# ESP32.net
KiCad netlist of a schematic drawn in Altium Designer
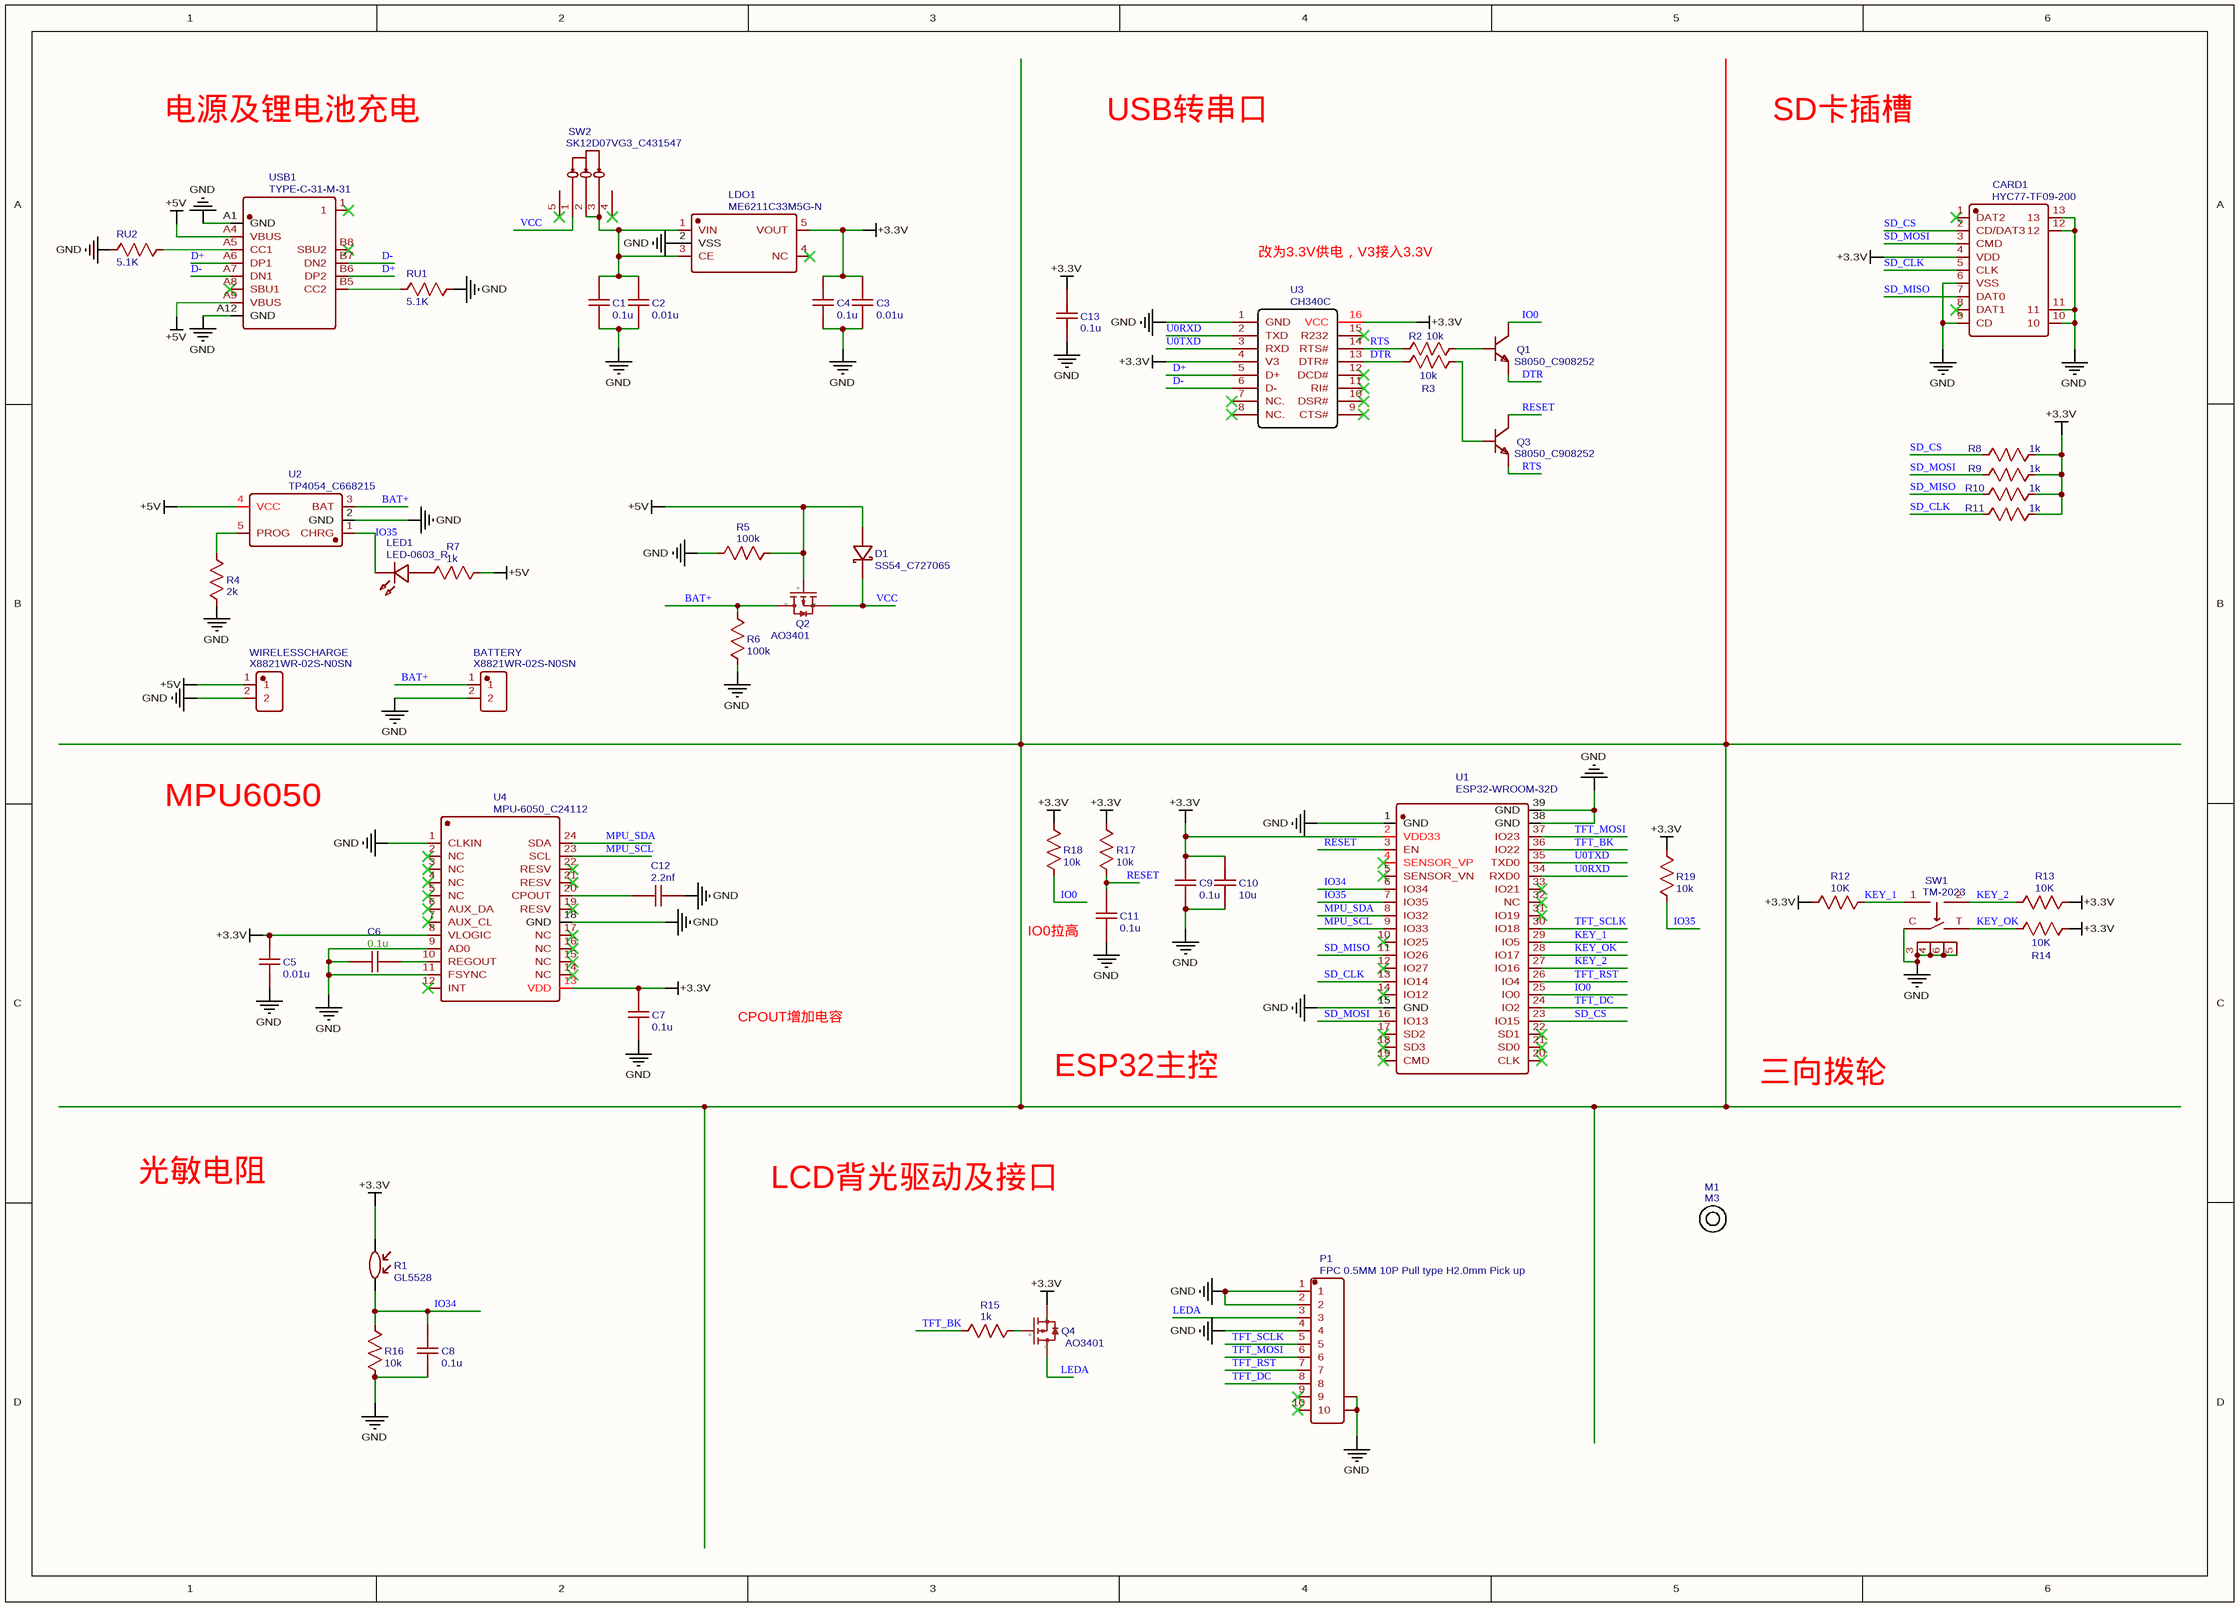
[diagram p0: ESP32花盆.schdoc]

(export (version "E")
  (design (tool "Eeschema 10.0.6"))
  (components
    (comp (ref "BATTERY")
      (value "X8821WR-02S-N0SN")
      (footprint "CONN-TH_X8821WR-02S-N0SN")
      (fields (field (name "BOM_SUPPLIER PART") "C388739") (field (name "CONTRIBUTOR") "LCSC"))
      (libsource (lib "altium-import") (part "root_0_X8821WR-02S-N0SN_"))
    )
    (comp (ref "C1")
      (value "0.1u")
      (footprint "C0603")
      (fields (field (name "CONTRIBUTOR") "LCEDA_Lib"))
      (libsource (lib "altium-import") (part "root_1_0.1u_"))
    )
    (comp (ref "C2")
      (value "0.01u")
      (footprint "C0603")
      (fields (field (name "CONTRIBUTOR") "LCEDA_Lib"))
      (libsource (lib "altium-import") (part "root_1_0.01u_"))
    )
    (comp (ref "C3")
      (value "0.01u")
      (footprint "C0603")
      (fields (field (name "CONTRIBUTOR") "LCEDA_Lib"))
      (libsource (lib "altium-import") (part "root_1_0.01u_"))
    )
    (comp (ref "C4")
      (value "0.1u")
      (footprint "C0603")
      (fields (field (name "CONTRIBUTOR") "LCEDA_Lib"))
      (libsource (lib "altium-import") (part "root_1_0.1u_"))
    )
    (comp (ref "C5")
      (value "0.01u")
      (footprint "C0603")
      (fields (field (name "CONTRIBUTOR") "LCEDA_Lib"))
      (libsource (lib "altium-import") (part "root_3_0.01u_"))
    )
    (comp (ref "C6")
      (value "0.1u")
      (footprint "C0603")
      (fields (field (name "CONTRIBUTOR") "LCEDA_Lib"))
      (libsource (lib "altium-import") (part "root_2_0.1u_"))
    )
    (comp (ref "C7")
      (value "0.1u")
      (footprint "C0603")
      (fields (field (name "CONTRIBUTOR") "LCEDA_Lib"))
      (libsource (lib "altium-import") (part "root_3_0.1u_"))
    )
    (comp (ref "C8")
      (value "0.1u")
      (footprint "C0603")
      (fields (field (name "CONTRIBUTOR") "LCEDA_Lib"))
      (libsource (lib "altium-import") (part "root_1_0.1u_"))
    )
    (comp (ref "C9")
      (value "0.1u")
      (footprint "C0603")
      (fields (field (name "CONTRIBUTOR") "LCEDA_Lib"))
      (libsource (lib "altium-import") (part "root_1_0.1u_"))
    )
    (comp (ref "C10")
      (value "10u")
      (footprint "C0603")
      (fields (field (name "CONTRIBUTOR") "LCEDA_Lib"))
      (libsource (lib "altium-import") (part "root_1_10u_"))
    )
    (comp (ref "C11")
      (value "0.1u")
      (footprint "C0603")
      (fields (field (name "CONTRIBUTOR") "LCEDA_Lib"))
      (libsource (lib "altium-import") (part "root_1_0.1u_"))
    )
    (comp (ref "C12")
      (value "2.2nf")
      (footprint "C0603")
      (fields (field (name "CONTRIBUTOR") "LCEDA_Lib"))
      (libsource (lib "altium-import") (part "root_0_2.2nf_"))
    )
    (comp (ref "C13")
      (value "0.1u")
      (footprint "C0603")
      (fields (field (name "CONTRIBUTOR") "LCEDA_Lib"))
      (libsource (lib "altium-import") (part "root_1_0.1u_"))
    )
    (comp (ref "CARD1")
      (value "HYC77-TF09-200")
      (footprint "TF-SMD_HYC77-TF09-200")
      (fields (field (name "BOM_SUPPLIER PART") "C341092") (field (name "CONTRIBUTOR") "LCSC"))
      (libsource (lib "altium-import") (part "root_0_HYC77-TF09-200_"))
    )
    (comp (ref "D1")
      (value "SS54_C727065")
      (footprint "SMA_L4.3-W2.6-LS5.0-RD")
      (fields
        (field (name "BOM_SUPPLIER PART") "C727065")
        (field (name "BOM_MANUFACTURER PART") "SS54")
        (field (name "CONTRIBUTOR") "LCSC")
      )
      (libsource (lib "altium-import") (part "root_1_SS54_C727065_"))
    )
    (comp (ref "LDO1")
      (value "ME6211C33M5G-N")
      (footprint "SOT-23-5_L3.0-W1.7-P0.95-LS2.8-BR")
      (fields (field (name "BOM_SUPPLIER PART") "C82942"))
      (libsource (lib "altium-import") (part "root_0_ME6211C33M5G-N_"))
    )
    (comp (ref "LED1")
      (value "LED-0603_R")
      (footprint "LED0603_RED")
      (fields
        (field (name "BOM_MANUFACTURER PART") "19-217/R6C-AL1M2VY/3T")
        (field (name "BOM_SUPPLIER PART") "C72044")
        (field (name "CONTRIBUTOR") "LCEDA_01")
      )
      (libsource (lib "altium-import") (part "root_2_LED-0603_R_"))
    )
    (comp (ref "M1")
      (value "M3")
      (footprint "M3")
      (fields (field (name "CONTRIBUTOR") "MengYang"))
      (libsource (lib "altium-import") (part "root_0_M3_"))
    )
    (comp (ref "P1")
      (value "FPC 0.5MM 10P Pull type H2.0mm Pick up")
      (footprint "FPC-SMD_FPC0.5MM10P")
      (fields (field (name "BOM_SUPPLIER PART") "C11085"))
      (libsource (lib "altium-import") (part "root_0_FPC 0.5MM 10P Pull type H2.0mm Pick up_"))
    )
    (comp (ref "Q1")
      (value "S8050_C908252")
      (footprint "SOT-23-3_L2.9-W1.3-P1.90-LS2.4-BR")
      (fields
        (field (name "BOM_SUPPLIER PART") "C908252")
        (field (name "BOM_MANUFACTURER PART") "S8050")
        (field (name "CONTRIBUTOR") "LCSC")
      )
      (libsource (lib "altium-import") (part "root_0_S8050_C908252_"))
    )
    (comp (ref "Q2")
      (value "AO3401")
      (footprint "SOT-23-3_L2.9-W1.3-P1.90-LS2.4-BR")
      (fields (field (name "BOM_SUPPLIER PART") "C181091") (field (name "CONTRIBUTOR") "LCSC"))
      (libsource (lib "altium-import") (part "root_3_AO3401_"))
    )
    (comp (ref "Q3")
      (value "S8050_C908252")
      (footprint "SOT-23-3_L2.9-W1.3-P1.90-LS2.4-BR")
      (fields
        (field (name "BOM_SUPPLIER PART") "C908252")
        (field (name "BOM_MANUFACTURER PART") "S8050")
        (field (name "CONTRIBUTOR") "LCSC")
      )
      (libsource (lib "altium-import") (part "root_0_S8050_C908252_"))
    )
    (comp (ref "Q4")
      (value "AO3401")
      (footprint "SOT-23-3_L2.9-W1.3-P1.90-LS2.4-BR")
      (fields (field (name "BOM_SUPPLIER PART") "C181091") (field (name "CONTRIBUTOR") "LCSC"))
      (libsource (lib "altium-import") (part "root_0_AO3401_"))
    )
    (comp (ref "R1")
      (value "GL5528")
      (footprint "RES-TH_L5.1-W4.3-P3.40-D0.5")
      (fields (field (name "BOM_SUPPLIER PART") "C125627"))
      (libsource (lib "altium-import") (part "root_3_GL5528_"))
    )
    (comp (ref "R2")
      (value "10k")
      (footprint "R0603")
      (fields (field (name "CONTRIBUTOR") "LCEDA_Lib"))
      (libsource (lib "altium-import") (part "root_0_10k_"))
    )
    (comp (ref "R3")
      (value "10k")
      (footprint "R0603")
      (fields (field (name "CONTRIBUTOR") "LCEDA_Lib"))
      (libsource (lib "altium-import") (part "root_0_10k_"))
    )
    (comp (ref "R4")
      (value "2k")
      (footprint "R0603")
      (fields (field (name "CONTRIBUTOR") "LCEDA_Lib"))
      (libsource (lib "altium-import") (part "root_1_2k_"))
    )
    (comp (ref "R5")
      (value "100k")
      (footprint "R0603")
      (fields (field (name "CONTRIBUTOR") "LCEDA_Lib"))
      (libsource (lib "altium-import") (part "root_0_100k_"))
    )
    (comp (ref "R6")
      (value "100k")
      (footprint "R0603")
      (fields (field (name "CONTRIBUTOR") "LCEDA_Lib"))
      (libsource (lib "altium-import") (part "root_1_100k_"))
    )
    (comp (ref "R7")
      (value "1k")
      (footprint "R0603")
      (fields (field (name "CONTRIBUTOR") "LCEDA_Lib"))
      (libsource (lib "altium-import") (part "root_0_1k_"))
    )
    (comp (ref "R8")
      (value "1k")
      (footprint "R0603")
      (fields (field (name "CONTRIBUTOR") "LCEDA_Lib"))
      (libsource (lib "altium-import") (part "root_0_1k_"))
    )
    (comp (ref "R9")
      (value "1k")
      (footprint "R0603")
      (fields (field (name "CONTRIBUTOR") "LCEDA_Lib"))
      (libsource (lib "altium-import") (part "root_0_1k_"))
    )
    (comp (ref "R10")
      (value "1k")
      (footprint "R0603")
      (fields (field (name "CONTRIBUTOR") "LCEDA_Lib"))
      (libsource (lib "altium-import") (part "root_0_1k_"))
    )
    (comp (ref "R11")
      (value "1k")
      (footprint "R0603")
      (fields (field (name "CONTRIBUTOR") "LCEDA_Lib"))
      (libsource (lib "altium-import") (part "root_0_1k_"))
    )
    (comp (ref "R12")
      (value "10K")
      (footprint "R0603")
      (fields (field (name "CONTRIBUTOR") "LCEDA_Lib"))
      (libsource (lib "altium-import") (part "root_2_10K_"))
    )
    (comp (ref "R13")
      (value "10K")
      (footprint "R0603")
      (fields (field (name "CONTRIBUTOR") "LCEDA_Lib"))
      (libsource (lib "altium-import") (part "root_2_10K_"))
    )
    (comp (ref "R14")
      (value "10K")
      (footprint "R0603")
      (fields (field (name "CONTRIBUTOR") "LCEDA_Lib"))
      (libsource (lib "altium-import") (part "root_2_10K_"))
    )
    (comp (ref "R15")
      (value "1k")
      (footprint "R0603")
      (fields (field (name "CONTRIBUTOR") "LCEDA_Lib"))
      (libsource (lib "altium-import") (part "root_0_1k_"))
    )
    (comp (ref "R16")
      (value "10k")
      (footprint "R0603")
      (fields (field (name "CONTRIBUTOR") "LCEDA_Lib"))
      (libsource (lib "altium-import") (part "root_1_10k_"))
    )
    (comp (ref "R17")
      (value "10k")
      (footprint "R0603")
      (fields (field (name "CONTRIBUTOR") "LCEDA_Lib"))
      (libsource (lib "altium-import") (part "root_1_10k_"))
    )
    (comp (ref "R18")
      (value "10k")
      (footprint "R0603")
      (fields (field (name "CONTRIBUTOR") "LCEDA_Lib"))
      (libsource (lib "altium-import") (part "root_1_10k_"))
    )
    (comp (ref "R19")
      (value "10k")
      (footprint "R0603")
      (fields (field (name "CONTRIBUTOR") "LCEDA_Lib"))
      (libsource (lib "altium-import") (part "root_1_10k_"))
    )
    (comp (ref "RU1")
      (value "5.1K")
      (footprint "R0603")
      (fields (field (name "CONTRIBUTOR") "LCEDA_Lib"))
      (libsource (lib "altium-import") (part "root_2_100k_"))
    )
    (comp (ref "RU2")
      (value "5.1K")
      (footprint "R0603")
      (fields (field (name "CONTRIBUTOR") "LCEDA_Lib"))
      (libsource (lib "altium-import") (part "root_2_100k_"))
    )
    (comp (ref "SW1")
      (value "TM-2023")
      (footprint "SW-SMD_TM-2023-1")
      (fields (field (name "BOM_SUPPLIER PART") "C318951") (field (name "CONTRIBUTOR") "LCSC"))
      (libsource (lib "altium-import") (part "root_0_TM-2023_"))
    )
    (comp (ref "SW2")
      (value "SK12D07VG3_C431547")
      (footprint "SW-TH_SK12D07VG3")
      (fields
        (field (name "BOM_SUPPLIER PART") "C431547")
        (field (name "BOM_MANUFACTURER PART") "SK12D07VG3")
        (field (name "CONTRIBUTOR") "LCSC")
      )
      (libsource (lib "altium-import") (part "root_0_SK12D07VG3_C431547_"))
    )
    (comp (ref "U1")
      (value "ESP32-WROOM-32D")
      (footprint "WIFIM-SMD_39P-L25.5-W18.0-P1.27-BL")
      (fields (field (name "BOM_SUPPLIER PART") "C473012") (field (name "CONTRIBUTOR") "LCSC"))
      (libsource (lib "altium-import") (part "root_0_ESP32-WROOM-32D_"))
    )
    (comp (ref "U2")
      (value "TP4054_C668215")
      (footprint "SOT-23-5_L3.0-W1.7-P0.95-LS2.8-BL")
      (fields
        (field (name "BOM_SUPPLIER PART") "C668215")
        (field (name "BOM_MANUFACTURER PART") "TP4054")
        (field (name "CONTRIBUTOR") "LCSC")
      )
      (libsource (lib "altium-import") (part "root_2_TP4054_C668215_"))
    )
    (comp (ref "U3")
      (value "CH340C")
      (footprint "SOP-16_L10.0-W3.9-P1.27-LS6.0-BL")
      (fields (field (name "BOM_SUPPLIER PART") "C84681"))
      (libsource (lib "altium-import") (part "root_0_CH340C_"))
    )
    (comp (ref "U4")
      (value "MPU-6050_C24112")
      (footprint "QFN-24_L4.0-W4.0-P0.50-BL-MPU-6050")
      (fields (field (name "BOM_MANUFACTURER PART") "MPU-6050") (field (name "BOM_SUPPLIER PART") "C24112"))
      (libsource (lib "altium-import") (part "root_0_MPU-6050_C24112_"))
    )
    (comp (ref "USB1")
      (value "TYPE-C-31-M-31")
      (footprint "USB-C-SMD_TYPE-C-31-M-31")
      (fields (field (name "BOM_SUPPLIER PART") "C2760486") (field (name "CONTRIBUTOR") "LCSC"))
      (libsource (lib "altium-import") (part "root_0_TYPE-C-31-M-31_"))
    )
    (comp (ref "WIRELESSCHARGE")
      (value "X8821WR-02S-N0SN")
      (footprint "CONN-TH_X8821WR-02S-N0SN")
      (fields (field (name "BOM_SUPPLIER PART") "C388739") (field (name "CONTRIBUTOR") "LCSC"))
      (libsource (lib "altium-import") (part "root_0_X8821WR-02S-N0SN_"))
    )
  )
  (nets
    (net (code "1") (name "+3.3V") (class "Default")
      (node (ref "C10") (pin "2") (pinfunction "2_2") (pintype "passive"))
      (node (ref "C13") (pin "2") (pinfunction "2_2") (pintype "passive"))
      (node (ref "C3") (pin "2") (pinfunction "2_2") (pintype "passive"))
      (node (ref "C4") (pin "2") (pinfunction "2_2") (pintype "passive"))
      (node (ref "C5") (pin "1") (pinfunction "1_1") (pintype "passive"))
      (node (ref "C7") (pin "1") (pinfunction "1_1") (pintype "passive"))
      (node (ref "C9") (pin "2") (pinfunction "2_2") (pintype "passive"))
      (node (ref "CARD1") (pin "4") (pinfunction "VDD_4") (pintype "passive"))
      (node (ref "LDO1") (pin "5") (pinfunction "VOUT_5") (pintype "passive"))
      (node (ref "Q4") (pin "2") (pinfunction "S_2") (pintype "passive"))
      (node (ref "R1") (pin "1") (pinfunction "1_1") (pintype "passive"))
      (node (ref "R10") (pin "2") (pinfunction "2_2") (pintype "passive"))
      (node (ref "R11") (pin "2") (pinfunction "2_2") (pintype "passive"))
      (node (ref "R12") (pin "2") (pinfunction "2_2") (pintype "passive"))
      (node (ref "R13") (pin "1") (pinfunction "1_1") (pintype "passive"))
      (node (ref "R14") (pin "1") (pinfunction "1_1") (pintype "passive"))
      (node (ref "R17") (pin "2") (pinfunction "2_2") (pintype "passive"))
      (node (ref "R18") (pin "2") (pinfunction "2_2") (pintype "passive"))
      (node (ref "R19") (pin "2") (pinfunction "2_2") (pintype "passive"))
      (node (ref "R8") (pin "2") (pinfunction "2_2") (pintype "passive"))
      (node (ref "R9") (pin "2") (pinfunction "2_2") (pintype "passive"))
      (node (ref "U1") (pin "2") (pinfunction "VDD33_2") (pintype "passive"))
      (node (ref "U3") (pin "16") (pinfunction "VCC_16") (pintype "passive"))
      (node (ref "U3") (pin "4") (pinfunction "V3_4") (pintype "passive"))
      (node (ref "U4") (pin "13") (pinfunction "VDD_13") (pintype "passive"))
      (node (ref "U4") (pin "8") (pinfunction "VLOGIC_8") (pintype "passive"))
    )
    (net (code "2") (name "+5V") (class "Default")
      (node (ref "D1") (pin "2") (pinfunction "2_2") (pintype "passive"))
      (node (ref "Q2") (pin "1") (pinfunction "G_1") (pintype "passive"))
      (node (ref "R5") (pin "2") (pinfunction "2_2") (pintype "passive"))
      (node (ref "R7") (pin "2") (pinfunction "2_2") (pintype "passive"))
      (node (ref "U2") (pin "4") (pinfunction "VCC_4") (pintype "passive"))
      (node (ref "USB1") (pin "A4") (pinfunction "VBUS_A4") (pintype "passive"))
      (node (ref "USB1") (pin "A9") (pinfunction "VBUS_A9") (pintype "passive"))
      (node (ref "WIRELESSCHARGE") (pin "1") (pinfunction "1_1") (pintype "passive"))
    )
    (net (code "3") (name "/BAT+") (class "Default")
      (node (ref "BATTERY") (pin "1") (pinfunction "1_1") (pintype "passive"))
      (node (ref "Q2") (pin "3") (pinfunction "D_3") (pintype "passive"))
      (node (ref "R6") (pin "2") (pinfunction "2_2") (pintype "passive"))
      (node (ref "U2") (pin "3") (pinfunction "BAT_3") (pintype "passive"))
    )
    (net (code "4") (name "/D+") (class "Default")
      (node (ref "U3") (pin "5") (pinfunction "D+_5") (pintype "passive"))
      (node (ref "USB1") (pin "A6") (pinfunction "DP1_A6") (pintype "passive"))
      (node (ref "USB1") (pin "B6") (pinfunction "DP2_B6") (pintype "passive"))
    )
    (net (code "5") (name "/D-") (class "Default")
      (node (ref "U3") (pin "6") (pinfunction "D-_6") (pintype "passive"))
      (node (ref "USB1") (pin "A7") (pinfunction "DN1_A7") (pintype "passive"))
      (node (ref "USB1") (pin "B7") (pinfunction "DN2_B7") (pintype "passive"))
    )
    (net (code "6") (name "/DTR") (class "Default")
      (node (ref "Q1") (pin "2") (pinfunction "E_2") (pintype "passive"))
      (node (ref "R3") (pin "1") (pinfunction "1_1") (pintype "passive"))
      (node (ref "U3") (pin "13") (pinfunction "DTR#_13") (pintype "passive"))
    )
    (net (code "7") (name "/IO0") (class "Default")
      (node (ref "Q1") (pin "3") (pinfunction "C_3") (pintype "passive"))
      (node (ref "R18") (pin "1") (pinfunction "1_1") (pintype "passive"))
      (node (ref "U1") (pin "25") (pinfunction "IO0_25") (pintype "passive"))
    )
    (net (code "8") (name "/IO34") (class "Default")
      (node (ref "C8") (pin "2") (pinfunction "2_2") (pintype "passive"))
      (node (ref "R1") (pin "2") (pinfunction "2_2") (pintype "passive"))
      (node (ref "R16") (pin "2") (pinfunction "2_2") (pintype "passive"))
      (node (ref "U1") (pin "6") (pinfunction "IO34_6") (pintype "passive"))
    )
    (net (code "9") (name "/IO35") (class "Default")
      (node (ref "LED1") (pin "2") (pinfunction "2_2") (pintype "passive"))
      (node (ref "R19") (pin "1") (pinfunction "1_1") (pintype "passive"))
      (node (ref "U1") (pin "7") (pinfunction "IO35_7") (pintype "passive"))
      (node (ref "U2") (pin "1") (pinfunction "CHRG_1") (pintype "passive"))
    )
    (net (code "10") (name "/KEY_1") (class "Default")
      (node (ref "R12") (pin "1") (pinfunction "1_1") (pintype "passive"))
      (node (ref "SW1") (pin "1") (pinfunction "1_1") (pintype "passive"))
      (node (ref "U1") (pin "29") (pinfunction "IO5_29") (pintype "passive"))
    )
    (net (code "11") (name "/KEY_2") (class "Default")
      (node (ref "R13") (pin "2") (pinfunction "2_2") (pintype "passive"))
      (node (ref "SW1") (pin "2") (pinfunction "2_2") (pintype "passive"))
      (node (ref "U1") (pin "27") (pinfunction "IO16_27") (pintype "passive"))
    )
    (net (code "12") (name "/KEY_OK") (class "Default")
      (node (ref "R14") (pin "2") (pinfunction "2_2") (pintype "passive"))
      (node (ref "SW1") (pin "T") (pinfunction "T_T") (pintype "passive"))
      (node (ref "U1") (pin "28") (pinfunction "IO17_28") (pintype "passive"))
    )
    (net (code "13") (name "/LEDA") (class "Default")
      (node (ref "P1") (pin "3") (pinfunction "3_3") (pintype "passive"))
      (node (ref "Q4") (pin "3") (pinfunction "D_3") (pintype "passive"))
    )
    (net (code "14") (name "/MPU_SCL") (class "Default")
      (node (ref "U1") (pin "9") (pinfunction "IO33_9") (pintype "passive"))
      (node (ref "U4") (pin "23") (pinfunction "SCL_23") (pintype "passive"))
    )
    (net (code "15") (name "/MPU_SDA") (class "Default")
      (node (ref "U1") (pin "8") (pinfunction "IO32_8") (pintype "passive"))
      (node (ref "U4") (pin "24") (pinfunction "SDA_24") (pintype "passive"))
    )
    (net (code "16") (name "/RESET") (class "Default")
      (node (ref "C11") (pin "2") (pinfunction "2_2") (pintype "passive"))
      (node (ref "Q3") (pin "3") (pinfunction "C_3") (pintype "passive"))
      (node (ref "R17") (pin "1") (pinfunction "1_1") (pintype "passive"))
      (node (ref "U1") (pin "3") (pinfunction "EN_3") (pintype "passive"))
    )
    (net (code "17") (name "/RTS") (class "Default")
      (node (ref "Q3") (pin "2") (pinfunction "E_2") (pintype "passive"))
      (node (ref "R2") (pin "1") (pinfunction "1_1") (pintype "passive"))
      (node (ref "U3") (pin "14") (pinfunction "RTS#_14") (pintype "passive"))
    )
    (net (code "18") (name "/SD_CLK") (class "Default")
      (node (ref "CARD1") (pin "5") (pinfunction "CLK_5") (pintype "passive"))
      (node (ref "R11") (pin "1") (pinfunction "1_1") (pintype "passive"))
      (node (ref "U1") (pin "13") (pinfunction "IO14_13") (pintype "passive"))
    )
    (net (code "19") (name "/SD_CS") (class "Default")
      (node (ref "CARD1") (pin "2") (pinfunction "CD/DAT3_2") (pintype "passive"))
      (node (ref "R8") (pin "1") (pinfunction "1_1") (pintype "passive"))
      (node (ref "U1") (pin "23") (pinfunction "IO15_23") (pintype "passive"))
    )
    (net (code "20") (name "/SD_MISO") (class "Default")
      (node (ref "CARD1") (pin "7") (pinfunction "DAT0_7") (pintype "passive"))
      (node (ref "R10") (pin "1") (pinfunction "1_1") (pintype "passive"))
      (node (ref "U1") (pin "11") (pinfunction "IO26_11") (pintype "passive"))
    )
    (net (code "21") (name "/SD_MOSI") (class "Default")
      (node (ref "CARD1") (pin "3") (pinfunction "CMD_3") (pintype "passive"))
      (node (ref "R9") (pin "1") (pinfunction "1_1") (pintype "passive"))
      (node (ref "U1") (pin "16") (pinfunction "IO13_16") (pintype "passive"))
    )
    (net (code "22") (name "/TFT_BK") (class "Default")
      (node (ref "R15") (pin "1") (pinfunction "1_1") (pintype "passive"))
      (node (ref "U1") (pin "36") (pinfunction "IO22_36") (pintype "passive"))
    )
    (net (code "23") (name "/TFT_DC") (class "Default")
      (node (ref "P1") (pin "8") (pinfunction "8_8") (pintype "passive"))
      (node (ref "U1") (pin "24") (pinfunction "IO2_24") (pintype "passive"))
    )
    (net (code "24") (name "/TFT_MOSI") (class "Default")
      (node (ref "P1") (pin "6") (pinfunction "6_6") (pintype "passive"))
      (node (ref "U1") (pin "37") (pinfunction "IO23_37") (pintype "passive"))
    )
    (net (code "25") (name "/TFT_RST") (class "Default")
      (node (ref "P1") (pin "7") (pinfunction "7_7") (pintype "passive"))
      (node (ref "U1") (pin "26") (pinfunction "IO4_26") (pintype "passive"))
    )
    (net (code "26") (name "/TFT_SCLK") (class "Default")
      (node (ref "P1") (pin "5") (pinfunction "5_5") (pintype "passive"))
      (node (ref "U1") (pin "30") (pinfunction "IO18_30") (pintype "passive"))
    )
    (net (code "27") (name "/U0RXD") (class "Default")
      (node (ref "U1") (pin "34") (pinfunction "RXD0_34") (pintype "passive"))
      (node (ref "U3") (pin "2") (pinfunction "TXD_2") (pintype "passive"))
    )
    (net (code "28") (name "/U0TXD") (class "Default")
      (node (ref "U1") (pin "35") (pinfunction "TXD0_35") (pintype "passive"))
      (node (ref "U3") (pin "3") (pinfunction "RXD_3") (pintype "passive"))
    )
    (net (code "29") (name "/VCC") (class "Default")
      (node (ref "D1") (pin "1") (pinfunction "1_1") (pintype "passive"))
      (node (ref "Q2") (pin "2") (pinfunction "S_2") (pintype "passive"))
      (node (ref "SW2") (pin "1") (pinfunction "1_1") (pintype "passive"))
    )
    (net (code "30") (name "GND") (class "Default")
      (node (ref "BATTERY") (pin "2") (pinfunction "2_2") (pintype "passive"))
      (node (ref "C1") (pin "1") (pinfunction "1_1") (pintype "passive"))
      (node (ref "C10") (pin "1") (pinfunction "1_1") (pintype "passive"))
      (node (ref "C11") (pin "1") (pinfunction "1_1") (pintype "passive"))
      (node (ref "C12") (pin "2") (pinfunction "2_2") (pintype "passive"))
      (node (ref "C13") (pin "1") (pinfunction "1_1") (pintype "passive"))
      (node (ref "C2") (pin "1") (pinfunction "1_1") (pintype "passive"))
      (node (ref "C3") (pin "1") (pinfunction "1_1") (pintype "passive"))
      (node (ref "C4") (pin "1") (pinfunction "1_1") (pintype "passive"))
      (node (ref "C5") (pin "2") (pinfunction "2_2") (pintype "passive"))
      (node (ref "C6") (pin "2") (pinfunction "2_2") (pintype "passive"))
      (node (ref "C7") (pin "2") (pinfunction "2_2") (pintype "passive"))
      (node (ref "C8") (pin "1") (pinfunction "1_1") (pintype "passive"))
      (node (ref "C9") (pin "1") (pinfunction "1_1") (pintype "passive"))
      (node (ref "CARD1") (pin "10") (pinfunction "10_10") (pintype "passive"))
      (node (ref "CARD1") (pin "11") (pinfunction "11_11") (pintype "passive"))
      (node (ref "CARD1") (pin "12") (pinfunction "12_12") (pintype "passive"))
      (node (ref "CARD1") (pin "13") (pinfunction "13_13") (pintype "passive"))
      (node (ref "CARD1") (pin "6") (pinfunction "VSS_6") (pintype "passive"))
      (node (ref "CARD1") (pin "9") (pinfunction "CD_9") (pintype "passive"))
      (node (ref "LDO1") (pin "2") (pinfunction "VSS_2") (pintype "passive"))
      (node (ref "P1") (pin "1") (pinfunction "1_1") (pintype "passive"))
      (node (ref "P1") (pin "11") (pinfunction "11_11") (pintype "passive"))
      (node (ref "P1") (pin "12") (pinfunction "12_12") (pintype "passive"))
      (node (ref "P1") (pin "2") (pinfunction "2_2") (pintype "passive"))
      (node (ref "P1") (pin "4") (pinfunction "4_4") (pintype "passive"))
      (node (ref "R16") (pin "1") (pinfunction "1_1") (pintype "passive"))
      (node (ref "R4") (pin "1") (pinfunction "1_1") (pintype "passive"))
      (node (ref "R5") (pin "1") (pinfunction "1_1") (pintype "passive"))
      (node (ref "R6") (pin "1") (pinfunction "1_1") (pintype "passive"))
      (node (ref "RU1") (pin "1") (pinfunction "1_1") (pintype "passive"))
      (node (ref "RU2") (pin "2") (pinfunction "2_2") (pintype "passive"))
      (node (ref "SW1") (pin "3") (pinfunction "3_3") (pintype "passive"))
      (node (ref "SW1") (pin "4") (pinfunction "4_4") (pintype "passive"))
      (node (ref "SW1") (pin "5") (pinfunction "5_5") (pintype "passive"))
      (node (ref "SW1") (pin "6") (pinfunction "6_6") (pintype "passive"))
      (node (ref "SW1") (pin "C") (pinfunction "C_C") (pintype "passive"))
      (node (ref "U1") (pin "1") (pinfunction "GND_1") (pintype "passive"))
      (node (ref "U1") (pin "15") (pinfunction "GND_15") (pintype "passive"))
      (node (ref "U1") (pin "38") (pinfunction "GND_38") (pintype "passive"))
      (node (ref "U1") (pin "39") (pinfunction "GND_39") (pintype "passive"))
      (node (ref "U2") (pin "2") (pinfunction "GND_2") (pintype "passive"))
      (node (ref "U3") (pin "1") (pinfunction "GND_1") (pintype "passive"))
      (node (ref "U4") (pin "1") (pinfunction "CLKIN_1") (pintype "passive"))
      (node (ref "U4") (pin "11") (pinfunction "FSYNC_11") (pintype "passive"))
      (node (ref "U4") (pin "18") (pinfunction "GND_18") (pintype "passive"))
      (node (ref "U4") (pin "9") (pinfunction "AD0_9") (pintype "passive"))
      (node (ref "USB1") (pin "A1") (pinfunction "GND_A1") (pintype "passive"))
      (node (ref "USB1") (pin "A12") (pinfunction "GND_A12") (pintype "passive"))
      (node (ref "WIRELESSCHARGE") (pin "2") (pinfunction "2_2") (pintype "passive"))
    )
    (net (code "31") (name "Net-(LDO1-CE)") (class "Default")
      (node (ref "C1") (pin "2") (pinfunction "2_2") (pintype "passive"))
      (node (ref "C2") (pin "2") (pinfunction "2_2") (pintype "passive"))
      (node (ref "LDO1") (pin "1") (pinfunction "VIN_1") (pintype "passive"))
      (node (ref "LDO1") (pin "3") (pinfunction "CE_3") (pintype "passive"))
      (node (ref "SW2") (pin "2") (pinfunction "2_2") (pintype "passive"))
      (node (ref "SW2") (pin "3") (pinfunction "3_3") (pintype "passive"))
    )
    (net (code "32") (name "Net-(LED1-Pad1)") (class "Default")
      (node (ref "LED1") (pin "1") (pinfunction "1_1") (pintype "passive"))
      (node (ref "R7") (pin "1") (pinfunction "1_1") (pintype "passive"))
    )
    (net (code "33") (name "Net-(Q1-B)") (class "Default")
      (node (ref "Q1") (pin "1") (pinfunction "B_1") (pintype "passive"))
      (node (ref "R2") (pin "2") (pinfunction "2_2") (pintype "passive"))
    )
    (net (code "34") (name "Net-(Q3-B)") (class "Default")
      (node (ref "Q3") (pin "1") (pinfunction "B_1") (pintype "passive"))
      (node (ref "R3") (pin "2") (pinfunction "2_2") (pintype "passive"))
    )
    (net (code "35") (name "Net-(Q4-G)") (class "Default")
      (node (ref "Q4") (pin "1") (pinfunction "G_1") (pintype "passive"))
      (node (ref "R15") (pin "2") (pinfunction "2_2") (pintype "passive"))
    )
    (net (code "36") (name "Net-(U2-PROG)") (class "Default")
      (node (ref "R4") (pin "2") (pinfunction "2_2") (pintype "passive"))
      (node (ref "U2") (pin "5") (pinfunction "PROG_5") (pintype "passive"))
    )
    (net (code "37") (name "Net-(U4-CPOUT)") (class "Default")
      (node (ref "C12") (pin "1") (pinfunction "1_1") (pintype "passive"))
      (node (ref "U4") (pin "20") (pinfunction "CPOUT_20") (pintype "passive"))
    )
    (net (code "38") (name "Net-(U4-REGOUT)") (class "Default")
      (node (ref "C6") (pin "1") (pinfunction "1_1") (pintype "passive"))
      (node (ref "U4") (pin "10") (pinfunction "REGOUT_10") (pintype "passive"))
    )
    (net (code "39") (name "Net-(USB1-CC1)") (class "Default")
      (node (ref "RU2") (pin "1") (pinfunction "1_1") (pintype "passive"))
      (node (ref "USB1") (pin "A5") (pinfunction "CC1_A5") (pintype "passive"))
    )
    (net (code "40") (name "Net-(USB1-CC2)") (class "Default")
      (node (ref "RU1") (pin "2") (pinfunction "2_2") (pintype "passive"))
      (node (ref "USB1") (pin "B5") (pinfunction "CC2_B5") (pintype "passive"))
    )
    (net (code "41") (name "unconnected-(CARD1-DAT1-Pad8)") (class "Default")
      (node (ref "CARD1") (pin "8") (pinfunction "DAT1_8") (pintype "passive+no_connect"))
    )
    (net (code "42") (name "unconnected-(CARD1-DAT2-Pad1)") (class "Default")
      (node (ref "CARD1") (pin "1") (pinfunction "DAT2_1") (pintype "passive+no_connect"))
    )
    (net (code "43") (name "unconnected-(LDO1-NC-Pad4)") (class "Default")
      (node (ref "LDO1") (pin "4") (pinfunction "NC_4") (pintype "passive+no_connect"))
    )
    (net (code "44") (name "unconnected-(P1-Pad9)") (class "Default")
      (node (ref "P1") (pin "9") (pinfunction "9_9") (pintype "passive+no_connect"))
    )
    (net (code "45") (name "unconnected-(P1-Pad10)") (class "Default")
      (node (ref "P1") (pin "10") (pinfunction "10_10") (pintype "passive+no_connect"))
    )
    (net (code "46") (name "unconnected-(SW2-Pad4)") (class "Default")
      (node (ref "SW2") (pin "4") (pinfunction "4_4") (pintype "passive+no_connect"))
    )
    (net (code "47") (name "unconnected-(SW2-Pad5)") (class "Default")
      (node (ref "SW2") (pin "5") (pinfunction "5_5") (pintype "passive+no_connect"))
    )
    (net (code "48") (name "unconnected-(U1-CLK-Pad20)") (class "Default")
      (node (ref "U1") (pin "20") (pinfunction "CLK_20") (pintype "passive+no_connect"))
    )
    (net (code "49") (name "unconnected-(U1-CMD-Pad19)") (class "Default")
      (node (ref "U1") (pin "19") (pinfunction "CMD_19") (pintype "passive+no_connect"))
    )
    (net (code "50") (name "unconnected-(U1-IO12-Pad14)") (class "Default")
      (node (ref "U1") (pin "14") (pinfunction "IO12_14") (pintype "passive+no_connect"))
    )
    (net (code "51") (name "unconnected-(U1-IO19-Pad31)") (class "Default")
      (node (ref "U1") (pin "31") (pinfunction "IO19_31") (pintype "passive+no_connect"))
    )
    (net (code "52") (name "unconnected-(U1-IO21-Pad33)") (class "Default")
      (node (ref "U1") (pin "33") (pinfunction "IO21_33") (pintype "passive+no_connect"))
    )
    (net (code "53") (name "unconnected-(U1-IO25-Pad10)") (class "Default")
      (node (ref "U1") (pin "10") (pinfunction "IO25_10") (pintype "passive+no_connect"))
    )
    (net (code "54") (name "unconnected-(U1-IO27-Pad12)") (class "Default")
      (node (ref "U1") (pin "12") (pinfunction "IO27_12") (pintype "passive+no_connect"))
    )
    (net (code "55") (name "unconnected-(U1-NC-Pad32)") (class "Default")
      (node (ref "U1") (pin "32") (pinfunction "NC_32") (pintype "passive+no_connect"))
    )
    (net (code "56") (name "unconnected-(U1-SD0-Pad21)") (class "Default")
      (node (ref "U1") (pin "21") (pinfunction "SD0_21") (pintype "passive+no_connect"))
    )
    (net (code "57") (name "unconnected-(U1-SD1-Pad22)") (class "Default")
      (node (ref "U1") (pin "22") (pinfunction "SD1_22") (pintype "passive+no_connect"))
    )
    (net (code "58") (name "unconnected-(U1-SD2-Pad17)") (class "Default")
      (node (ref "U1") (pin "17") (pinfunction "SD2_17") (pintype "passive+no_connect"))
    )
    (net (code "59") (name "unconnected-(U1-SD3-Pad18)") (class "Default")
      (node (ref "U1") (pin "18") (pinfunction "SD3_18") (pintype "passive+no_connect"))
    )
    (net (code "60") (name "unconnected-(U1-SENSOR_VN-Pad5)") (class "Default")
      (node (ref "U1") (pin "5") (pinfunction "SENSOR_VN_5") (pintype "passive+no_connect"))
    )
    (net (code "61") (name "unconnected-(U1-SENSOR_VP-Pad4)") (class "Default")
      (node (ref "U1") (pin "4") (pinfunction "SENSOR_VP_4") (pintype "passive+no_connect"))
    )
    (net (code "62") (name "unconnected-(U3-CTS#-Pad9)") (class "Default")
      (node (ref "U3") (pin "9") (pinfunction "CTS#_9") (pintype "passive+no_connect"))
    )
    (net (code "63") (name "unconnected-(U3-DCD#-Pad12)") (class "Default")
      (node (ref "U3") (pin "12") (pinfunction "DCD#_12") (pintype "passive+no_connect"))
    )
    (net (code "64") (name "unconnected-(U3-DSR#-Pad10)") (class "Default")
      (node (ref "U3") (pin "10") (pinfunction "DSR#_10") (pintype "passive+no_connect"))
    )
    (net (code "65") (name "unconnected-(U3-NC.-Pad7)") (class "Default")
      (node (ref "U3") (pin "7") (pinfunction "NC._7") (pintype "passive+no_connect"))
    )
    (net (code "66") (name "unconnected-(U3-NC.-Pad8)") (class "Default")
      (node (ref "U3") (pin "8") (pinfunction "NC._8") (pintype "passive+no_connect"))
    )
    (net (code "67") (name "unconnected-(U3-R232-Pad15)") (class "Default")
      (node (ref "U3") (pin "15") (pinfunction "R232_15") (pintype "passive+no_connect"))
    )
    (net (code "68") (name "unconnected-(U3-RI#-Pad11)") (class "Default")
      (node (ref "U3") (pin "11") (pinfunction "RI#_11") (pintype "passive+no_connect"))
    )
    (net (code "69") (name "unconnected-(U4-AUX_CL-Pad7)") (class "Default")
      (node (ref "U4") (pin "7") (pinfunction "AUX_CL_7") (pintype "passive+no_connect"))
    )
    (net (code "70") (name "unconnected-(U4-AUX_DA-Pad6)") (class "Default")
      (node (ref "U4") (pin "6") (pinfunction "AUX_DA_6") (pintype "passive+no_connect"))
    )
    (net (code "71") (name "unconnected-(U4-INT-Pad12)") (class "Default")
      (node (ref "U4") (pin "12") (pinfunction "INT_12") (pintype "passive+no_connect"))
    )
    (net (code "72") (name "unconnected-(U4-NC-Pad2)") (class "Default")
      (node (ref "U4") (pin "2") (pinfunction "NC_2") (pintype "passive+no_connect"))
    )
    (net (code "73") (name "unconnected-(U4-NC-Pad3)") (class "Default")
      (node (ref "U4") (pin "3") (pinfunction "NC_3") (pintype "passive+no_connect"))
    )
    (net (code "74") (name "unconnected-(U4-NC-Pad4)") (class "Default")
      (node (ref "U4") (pin "4") (pinfunction "NC_4") (pintype "passive+no_connect"))
    )
    (net (code "75") (name "unconnected-(U4-NC-Pad5)") (class "Default")
      (node (ref "U4") (pin "5") (pinfunction "NC_5") (pintype "passive+no_connect"))
    )
    (net (code "76") (name "unconnected-(U4-NC-Pad14)") (class "Default")
      (node (ref "U4") (pin "14") (pinfunction "NC_14") (pintype "passive+no_connect"))
    )
    (net (code "77") (name "unconnected-(U4-NC-Pad15)") (class "Default")
      (node (ref "U4") (pin "15") (pinfunction "NC_15") (pintype "passive+no_connect"))
    )
    (net (code "78") (name "unconnected-(U4-NC-Pad16)") (class "Default")
      (node (ref "U4") (pin "16") (pinfunction "NC_16") (pintype "passive+no_connect"))
    )
    (net (code "79") (name "unconnected-(U4-NC-Pad17)") (class "Default")
      (node (ref "U4") (pin "17") (pinfunction "NC_17") (pintype "passive+no_connect"))
    )
    (net (code "80") (name "unconnected-(U4-RESV-Pad19)") (class "Default")
      (node (ref "U4") (pin "19") (pinfunction "RESV_19") (pintype "passive+no_connect"))
    )
    (net (code "81") (name "unconnected-(U4-RESV-Pad21)") (class "Default")
      (node (ref "U4") (pin "21") (pinfunction "RESV_21") (pintype "passive+no_connect"))
    )
    (net (code "82") (name "unconnected-(U4-RESV-Pad22)") (class "Default")
      (node (ref "U4") (pin "22") (pinfunction "RESV_22") (pintype "passive+no_connect"))
    )
    (net (code "83") (name "unconnected-(USB1-Pad1)") (class "Default")
      (node (ref "USB1") (pin "1") (pinfunction "1_1") (pintype "passive+no_connect"))
    )
    (net (code "84") (name "unconnected-(USB1-SBU1-PadA8)") (class "Default")
      (node (ref "USB1") (pin "A8") (pinfunction "SBU1_A8") (pintype "passive+no_connect"))
    )
    (net (code "85") (name "unconnected-(USB1-SBU2-PadB8)") (class "Default")
      (node (ref "USB1") (pin "B8") (pinfunction "SBU2_B8") (pintype "passive+no_connect"))
    )
  )
)
